# tube-driver.net
KiCad netlist of a schematic drawn in Altium Designer
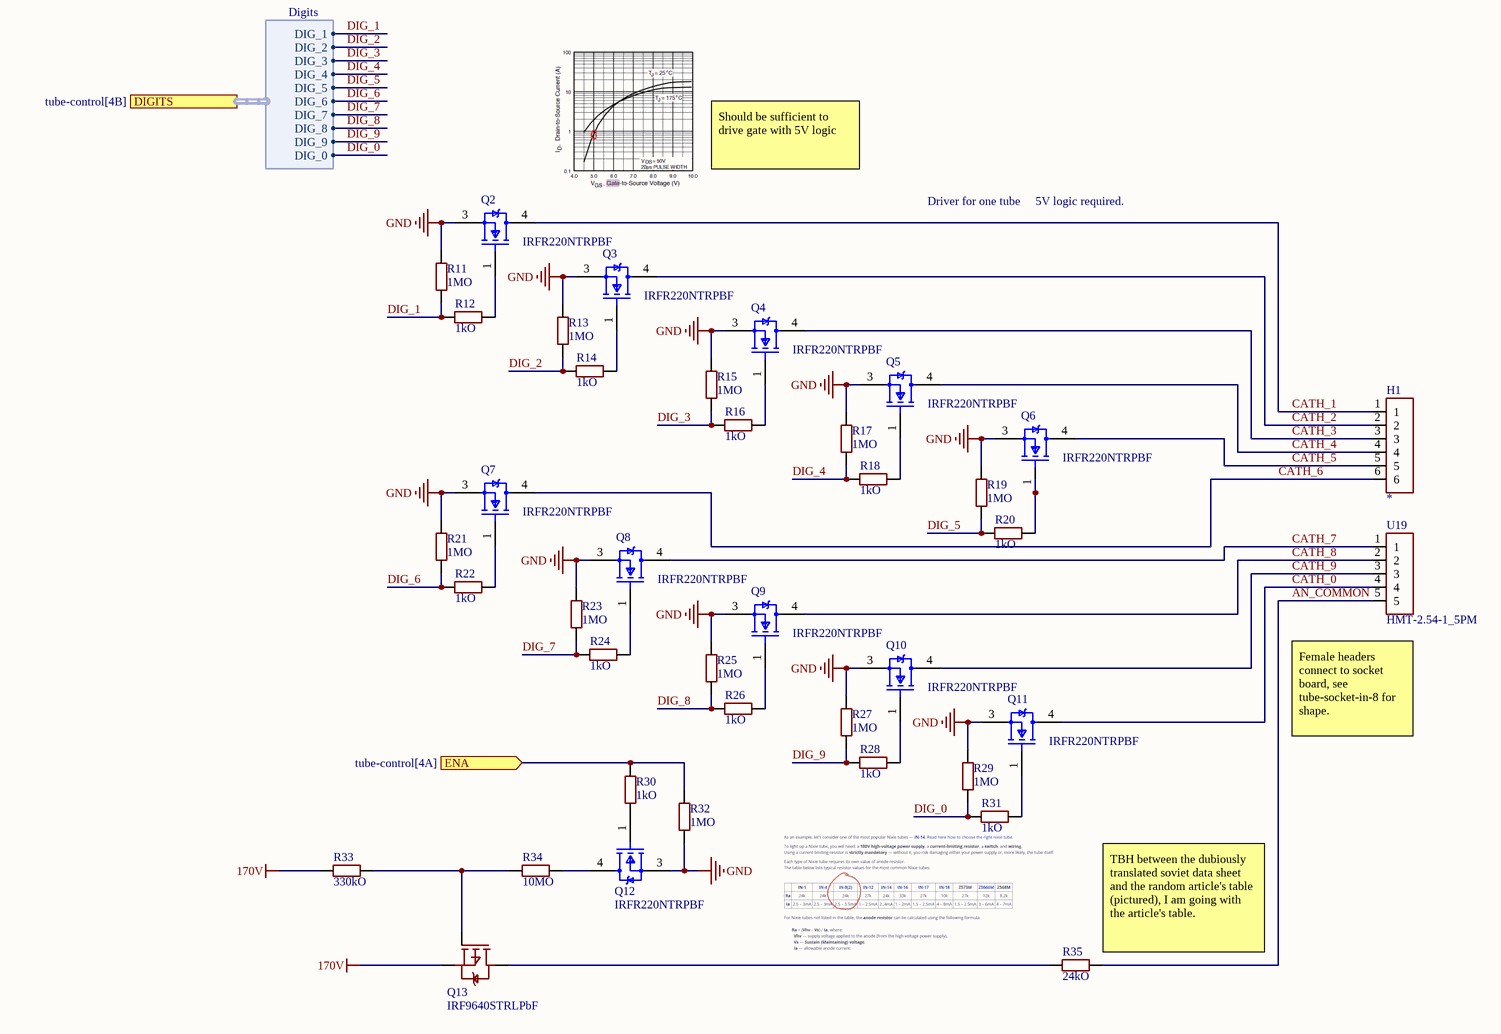
[diagram p0: tube-driver.SchDoc]

(export (version "E")
  (design (tool "Eeschema 10.0.6"))
  (components
    (comp (ref "H1")
      (value "2.54-1_6P")
      (footprint "2.54-1_6P")
      (fields
        (field (name "ALTIUM_VALUE") "*")
        (field (name "JLCPCB PART #") "C40877")
        (field (name "MANUFACTURER PART NUMBER") "2.54-1*6P")
        (field (name "MANUFACTURER") "BOOMELE(Boom Precision Elec)")
      )
      (libsource (lib "2.54-1_6P") (part "2.54-1_6P"))
    )
    (comp (ref "Q2")
      (value "IRFR220NTRPBF")
      (footprint "FP-PG-TO252-3-MFG")
      (description "MOSFET N-CH 200V 5A DPAK")
      (fields
        (field (name "MANUFACTURER") "Infineon")
        (field (name "OCTOPART") "https://octopart.com/irfr220ntrpbf-infineon-65874086")
      )
      (libsource (lib "Altium Content Vault") (part "2f21c11e83d30f418bb422e5a3b3d11"))
    )
    (comp (ref "Q3")
      (value "IRFR220NTRPBF")
      (footprint "FP-PG-TO252-3-MFG")
      (description "MOSFET N-CH 200V 5A DPAK")
      (fields
        (field (name "MANUFACTURER") "Infineon")
        (field (name "OCTOPART") "https://octopart.com/irfr220ntrpbf-infineon-65874086")
      )
      (libsource (lib "Altium Content Vault") (part "2f21c11e83d30f418bb422e5a3b3d11"))
    )
    (comp (ref "Q4")
      (value "IRFR220NTRPBF")
      (footprint "FP-PG-TO252-3-MFG")
      (description "MOSFET N-CH 200V 5A DPAK")
      (fields
        (field (name "MANUFACTURER") "Infineon")
        (field (name "OCTOPART") "https://octopart.com/irfr220ntrpbf-infineon-65874086")
      )
      (libsource (lib "Altium Content Vault") (part "2f21c11e83d30f418bb422e5a3b3d11"))
    )
    (comp (ref "Q5")
      (value "IRFR220NTRPBF")
      (footprint "FP-PG-TO252-3-MFG")
      (description "MOSFET N-CH 200V 5A DPAK")
      (fields
        (field (name "MANUFACTURER") "Infineon")
        (field (name "OCTOPART") "https://octopart.com/irfr220ntrpbf-infineon-65874086")
      )
      (libsource (lib "Altium Content Vault") (part "2f21c11e83d30f418bb422e5a3b3d11"))
    )
    (comp (ref "Q6")
      (value "IRFR220NTRPBF")
      (footprint "FP-PG-TO252-3-MFG")
      (description "MOSFET N-CH 200V 5A DPAK")
      (fields
        (field (name "MANUFACTURER") "Infineon")
        (field (name "OCTOPART") "https://octopart.com/irfr220ntrpbf-infineon-65874086")
      )
      (libsource (lib "Altium Content Vault") (part "2f21c11e83d30f418bb422e5a3b3d11"))
    )
    (comp (ref "Q7")
      (value "IRFR220NTRPBF")
      (footprint "FP-PG-TO252-3-MFG")
      (description "MOSFET N-CH 200V 5A DPAK")
      (fields
        (field (name "MANUFACTURER") "Infineon")
        (field (name "OCTOPART") "https://octopart.com/irfr220ntrpbf-infineon-65874086")
      )
      (libsource (lib "Altium Content Vault") (part "2f21c11e83d30f418bb422e5a3b3d11"))
    )
    (comp (ref "Q8")
      (value "IRFR220NTRPBF")
      (footprint "FP-PG-TO252-3-MFG")
      (description "MOSFET N-CH 200V 5A DPAK")
      (fields
        (field (name "MANUFACTURER") "Infineon")
        (field (name "OCTOPART") "https://octopart.com/irfr220ntrpbf-infineon-65874086")
      )
      (libsource (lib "Altium Content Vault") (part "2f21c11e83d30f418bb422e5a3b3d11"))
    )
    (comp (ref "Q9")
      (value "IRFR220NTRPBF")
      (footprint "FP-PG-TO252-3-MFG")
      (description "MOSFET N-CH 200V 5A DPAK")
      (fields
        (field (name "MANUFACTURER") "Infineon")
        (field (name "OCTOPART") "https://octopart.com/irfr220ntrpbf-infineon-65874086")
      )
      (libsource (lib "Altium Content Vault") (part "2f21c11e83d30f418bb422e5a3b3d11"))
    )
    (comp (ref "Q10")
      (value "IRFR220NTRPBF")
      (footprint "FP-PG-TO252-3-MFG")
      (description "MOSFET N-CH 200V 5A DPAK")
      (fields
        (field (name "MANUFACTURER") "Infineon")
        (field (name "OCTOPART") "https://octopart.com/irfr220ntrpbf-infineon-65874086")
      )
      (libsource (lib "Altium Content Vault") (part "2f21c11e83d30f418bb422e5a3b3d11"))
    )
    (comp (ref "Q11")
      (value "IRFR220NTRPBF")
      (footprint "FP-PG-TO252-3-MFG")
      (description "MOSFET N-CH 200V 5A DPAK")
      (fields
        (field (name "MANUFACTURER") "Infineon")
        (field (name "OCTOPART") "https://octopart.com/irfr220ntrpbf-infineon-65874086")
      )
      (libsource (lib "Altium Content Vault") (part "2f21c11e83d30f418bb422e5a3b3d11"))
    )
    (comp (ref "Q12")
      (value "IRFR220NTRPBF")
      (footprint "FP-PG-TO252-3-MFG")
      (description "MOSFET N-CH 200V 5A DPAK")
      (fields
        (field (name "MANUFACTURER") "Infineon")
        (field (name "OCTOPART") "https://octopart.com/irfr220ntrpbf-infineon-65874086")
      )
      (libsource (lib "Altium Content Vault") (part "2f21c11e83d30f418bb422e5a3b3d11"))
    )
    (comp (ref "Q13")
      (value "IRF9640STRLPbF")
      (footprint "IRF9640STRLPbF")
      (fields (field (name "JLCPCB PART #") "C2629") (field (name "MANUFACTURER") "Vishay Intertech"))
      (libsource (lib "IRF9640STRLPbF") (part "IRF9640STRLPbF"))
    )
    (comp (ref "R11")
      (value "1MO")
      (footprint "0402WGF1004TCE")
      (fields
        (field (name "JLCPCB PART #") "C26083")
        (field (name "MANUFACTURER PART NUMBER") "0402WGF1004TCE")
        (field (name "MANUFACTURER") "UNI-ROYAL(Uniroyal Elec)")
      )
      (libsource (lib "0402WGF1004TCE") (part "0402WGF1004TCE"))
    )
    (comp (ref "R12")
      (value "1kO")
      (footprint "0402WGF1001TCE")
      (fields
        (field (name "JLCPCB PART #") "C11702")
        (field (name "MANUFACTURER PART NUMBER") "0402WGF1001TCE")
        (field (name "MANUFACTURER") "UNI-ROYAL(Uniroyal Elec)")
      )
      (libsource (lib "0402WGF1001TCE") (part "0402WGF1001TCE"))
    )
    (comp (ref "R13")
      (value "1MO")
      (footprint "0402WGF1004TCE")
      (fields
        (field (name "JLCPCB PART #") "C26083")
        (field (name "MANUFACTURER PART NUMBER") "0402WGF1004TCE")
        (field (name "MANUFACTURER") "UNI-ROYAL(Uniroyal Elec)")
      )
      (libsource (lib "0402WGF1004TCE") (part "0402WGF1004TCE"))
    )
    (comp (ref "R14")
      (value "1kO")
      (footprint "0402WGF1001TCE")
      (fields
        (field (name "JLCPCB PART #") "C11702")
        (field (name "MANUFACTURER PART NUMBER") "0402WGF1001TCE")
        (field (name "MANUFACTURER") "UNI-ROYAL(Uniroyal Elec)")
      )
      (libsource (lib "0402WGF1001TCE") (part "0402WGF1001TCE"))
    )
    (comp (ref "R15")
      (value "1MO")
      (footprint "0402WGF1004TCE")
      (fields
        (field (name "JLCPCB PART #") "C26083")
        (field (name "MANUFACTURER PART NUMBER") "0402WGF1004TCE")
        (field (name "MANUFACTURER") "UNI-ROYAL(Uniroyal Elec)")
      )
      (libsource (lib "0402WGF1004TCE") (part "0402WGF1004TCE"))
    )
    (comp (ref "R16")
      (value "1kO")
      (footprint "0402WGF1001TCE")
      (fields
        (field (name "JLCPCB PART #") "C11702")
        (field (name "MANUFACTURER PART NUMBER") "0402WGF1001TCE")
        (field (name "MANUFACTURER") "UNI-ROYAL(Uniroyal Elec)")
      )
      (libsource (lib "0402WGF1001TCE") (part "0402WGF1001TCE"))
    )
    (comp (ref "R17")
      (value "1MO")
      (footprint "0402WGF1004TCE")
      (fields
        (field (name "JLCPCB PART #") "C26083")
        (field (name "MANUFACTURER PART NUMBER") "0402WGF1004TCE")
        (field (name "MANUFACTURER") "UNI-ROYAL(Uniroyal Elec)")
      )
      (libsource (lib "0402WGF1004TCE") (part "0402WGF1004TCE"))
    )
    (comp (ref "R18")
      (value "1kO")
      (footprint "0402WGF1001TCE")
      (fields
        (field (name "JLCPCB PART #") "C11702")
        (field (name "MANUFACTURER PART NUMBER") "0402WGF1001TCE")
        (field (name "MANUFACTURER") "UNI-ROYAL(Uniroyal Elec)")
      )
      (libsource (lib "0402WGF1001TCE") (part "0402WGF1001TCE"))
    )
    (comp (ref "R19")
      (value "1MO")
      (footprint "0402WGF1004TCE")
      (fields
        (field (name "JLCPCB PART #") "C26083")
        (field (name "MANUFACTURER PART NUMBER") "0402WGF1004TCE")
        (field (name "MANUFACTURER") "UNI-ROYAL(Uniroyal Elec)")
      )
      (libsource (lib "0402WGF1004TCE") (part "0402WGF1004TCE"))
    )
    (comp (ref "R20")
      (value "1kO")
      (footprint "0402WGF1001TCE")
      (fields
        (field (name "JLCPCB PART #") "C11702")
        (field (name "MANUFACTURER PART NUMBER") "0402WGF1001TCE")
        (field (name "MANUFACTURER") "UNI-ROYAL(Uniroyal Elec)")
      )
      (libsource (lib "0402WGF1001TCE") (part "0402WGF1001TCE"))
    )
    (comp (ref "R21")
      (value "1MO")
      (footprint "0402WGF1004TCE")
      (fields
        (field (name "JLCPCB PART #") "C26083")
        (field (name "MANUFACTURER PART NUMBER") "0402WGF1004TCE")
        (field (name "MANUFACTURER") "UNI-ROYAL(Uniroyal Elec)")
      )
      (libsource (lib "0402WGF1004TCE") (part "0402WGF1004TCE"))
    )
    (comp (ref "R22")
      (value "1kO")
      (footprint "0402WGF1001TCE")
      (fields
        (field (name "JLCPCB PART #") "C11702")
        (field (name "MANUFACTURER PART NUMBER") "0402WGF1001TCE")
        (field (name "MANUFACTURER") "UNI-ROYAL(Uniroyal Elec)")
      )
      (libsource (lib "0402WGF1001TCE") (part "0402WGF1001TCE"))
    )
    (comp (ref "R23")
      (value "1MO")
      (footprint "0402WGF1004TCE")
      (fields
        (field (name "JLCPCB PART #") "C26083")
        (field (name "MANUFACTURER PART NUMBER") "0402WGF1004TCE")
        (field (name "MANUFACTURER") "UNI-ROYAL(Uniroyal Elec)")
      )
      (libsource (lib "0402WGF1004TCE") (part "0402WGF1004TCE"))
    )
    (comp (ref "R24")
      (value "1kO")
      (footprint "0402WGF1001TCE")
      (fields
        (field (name "JLCPCB PART #") "C11702")
        (field (name "MANUFACTURER PART NUMBER") "0402WGF1001TCE")
        (field (name "MANUFACTURER") "UNI-ROYAL(Uniroyal Elec)")
      )
      (libsource (lib "0402WGF1001TCE") (part "0402WGF1001TCE"))
    )
    (comp (ref "R25")
      (value "1MO")
      (footprint "0402WGF1004TCE")
      (fields
        (field (name "JLCPCB PART #") "C26083")
        (field (name "MANUFACTURER PART NUMBER") "0402WGF1004TCE")
        (field (name "MANUFACTURER") "UNI-ROYAL(Uniroyal Elec)")
      )
      (libsource (lib "0402WGF1004TCE") (part "0402WGF1004TCE"))
    )
    (comp (ref "R26")
      (value "1kO")
      (footprint "0402WGF1001TCE")
      (fields
        (field (name "JLCPCB PART #") "C11702")
        (field (name "MANUFACTURER PART NUMBER") "0402WGF1001TCE")
        (field (name "MANUFACTURER") "UNI-ROYAL(Uniroyal Elec)")
      )
      (libsource (lib "0402WGF1001TCE") (part "0402WGF1001TCE"))
    )
    (comp (ref "R27")
      (value "1MO")
      (footprint "0402WGF1004TCE")
      (fields
        (field (name "JLCPCB PART #") "C26083")
        (field (name "MANUFACTURER PART NUMBER") "0402WGF1004TCE")
        (field (name "MANUFACTURER") "UNI-ROYAL(Uniroyal Elec)")
      )
      (libsource (lib "0402WGF1004TCE") (part "0402WGF1004TCE"))
    )
    (comp (ref "R28")
      (value "1kO")
      (footprint "0402WGF1001TCE")
      (fields
        (field (name "JLCPCB PART #") "C11702")
        (field (name "MANUFACTURER PART NUMBER") "0402WGF1001TCE")
        (field (name "MANUFACTURER") "UNI-ROYAL(Uniroyal Elec)")
      )
      (libsource (lib "0402WGF1001TCE") (part "0402WGF1001TCE"))
    )
    (comp (ref "R29")
      (value "1MO")
      (footprint "0402WGF1004TCE")
      (fields
        (field (name "JLCPCB PART #") "C26083")
        (field (name "MANUFACTURER PART NUMBER") "0402WGF1004TCE")
        (field (name "MANUFACTURER") "UNI-ROYAL(Uniroyal Elec)")
      )
      (libsource (lib "0402WGF1004TCE") (part "0402WGF1004TCE"))
    )
    (comp (ref "R30")
      (value "1kO")
      (footprint "0402WGF1001TCE")
      (fields
        (field (name "JLCPCB PART #") "C11702")
        (field (name "MANUFACTURER PART NUMBER") "0402WGF1001TCE")
        (field (name "MANUFACTURER") "UNI-ROYAL(Uniroyal Elec)")
      )
      (libsource (lib "") (part "0402WGF1001TCE_1"))
    )
    (comp (ref "R31")
      (value "1kO")
      (footprint "0402WGF1001TCE")
      (fields
        (field (name "JLCPCB PART #") "C11702")
        (field (name "MANUFACTURER PART NUMBER") "0402WGF1001TCE")
        (field (name "MANUFACTURER") "UNI-ROYAL(Uniroyal Elec)")
      )
      (libsource (lib "0402WGF1001TCE") (part "0402WGF1001TCE"))
    )
    (comp (ref "R32")
      (value "1MO")
      (footprint "0402WGF1004TCE")
      (fields
        (field (name "JLCPCB PART #") "C26083")
        (field (name "MANUFACTURER PART NUMBER") "0402WGF1004TCE")
        (field (name "MANUFACTURER") "UNI-ROYAL(Uniroyal Elec)")
      )
      (libsource (lib "0402WGF1004TCE") (part "0402WGF1004TCE"))
    )
    (comp (ref "R33")
      (value "330kO")
      (footprint "0603WAF3303T5E")
      (fields
        (field (name "JLCPCB PART #") "C23137")
        (field (name "MANUFACTURER PART NUMBER") "0603WAF3303T5E")
        (field (name "MANUFACTURER") "UNI-ROYAL(Uniroyal Elec)")
      )
      (libsource (lib "0603WAF3303T5E") (part "0603WAF3303T5E"))
    )
    (comp (ref "R34")
      (value "10MO")
      (footprint "0603WAF1005T5E")
      (fields
        (field (name "JLCPCB PART #") "C7250")
        (field (name "MANUFACTURER PART NUMBER") "0603WAF1005T5E")
        (field (name "MANUFACTURER") "UNI-ROYAL(Uniroyal Elec)")
      )
      (libsource (lib "0603WAF1005T5E") (part "0603WAF1005T5E"))
    )
    (comp (ref "R35")
      (value "24kO")
      (footprint "0603WAF2402T5E")
      (fields
        (field (name "JLCPCB PART #") "C23352")
        (field (name "MANUFACTURER PART NUMBER") "0603WAF2402T5E")
        (field (name "MANUFACTURER") "UNI-ROYAL(Uniroyal Elec)")
      )
      (libsource (lib "0603WAF2402T5E") (part "0603WAF2402T5E"))
    )
    (comp (ref "U19")
      (value "HMT-2.54-1_5PM")
      (footprint "HMT-2.54-1_5PM")
      (fields
        (field (name "JLCPCB PART #") "C54620386")
        (field (name "MANUFACTURER PART NUMBER") "HMT-2.54-1*5PM")
        (field (name "MANUFACTURER") "HMTCONN")
      )
      (libsource (lib "HMT-2.54-1_5PM") (part "HMT-2.54-1_5PM"))
    )
  )
  (nets
    (net (code "2") (name "/AN_COMMON") (class "Default")
      (node (ref "R35") (pin "2") (pinfunction "2_2") (pintype "passive"))
      (node (ref "U19") (pin "5") (pinfunction "5_5") (pintype "passive"))
    )
    (net (code "3") (name "/CATH_0") (class "Default")
      (node (ref "Q11") (pin "4") (pinfunction "DRAIN_4") (pintype "passive"))
      (node (ref "U19") (pin "4") (pinfunction "4_4") (pintype "passive"))
    )
    (net (code "4") (name "/CATH_1") (class "Default")
      (node (ref "H1") (pin "1") (pinfunction "1_1") (pintype "passive"))
      (node (ref "Q2") (pin "4") (pinfunction "DRAIN_4") (pintype "passive"))
    )
    (net (code "5") (name "/CATH_2") (class "Default")
      (node (ref "H1") (pin "2") (pinfunction "2_2") (pintype "passive"))
      (node (ref "Q3") (pin "4") (pinfunction "DRAIN_4") (pintype "passive"))
    )
    (net (code "6") (name "/CATH_3") (class "Default")
      (node (ref "H1") (pin "3") (pinfunction "3_3") (pintype "passive"))
      (node (ref "Q4") (pin "4") (pinfunction "DRAIN_4") (pintype "passive"))
    )
    (net (code "7") (name "/CATH_4") (class "Default")
      (node (ref "H1") (pin "4") (pinfunction "4_4") (pintype "passive"))
      (node (ref "Q5") (pin "4") (pinfunction "DRAIN_4") (pintype "passive"))
    )
    (net (code "8") (name "/CATH_5") (class "Default")
      (node (ref "H1") (pin "5") (pinfunction "5_5") (pintype "passive"))
      (node (ref "Q6") (pin "4") (pinfunction "DRAIN_4") (pintype "passive"))
    )
    (net (code "9") (name "/CATH_6") (class "Default")
      (node (ref "H1") (pin "6") (pinfunction "6_6") (pintype "passive"))
      (node (ref "Q7") (pin "4") (pinfunction "DRAIN_4") (pintype "passive"))
    )
    (net (code "10") (name "/CATH_7") (class "Default")
      (node (ref "Q8") (pin "4") (pinfunction "DRAIN_4") (pintype "passive"))
      (node (ref "U19") (pin "1") (pinfunction "1_1") (pintype "passive"))
    )
    (net (code "11") (name "/CATH_8") (class "Default")
      (node (ref "Q9") (pin "4") (pinfunction "DRAIN_4") (pintype "passive"))
      (node (ref "U19") (pin "2") (pinfunction "2_2") (pintype "passive"))
    )
    (net (code "12") (name "/CATH_9") (class "Default")
      (node (ref "Q10") (pin "4") (pinfunction "DRAIN_4") (pintype "passive"))
      (node (ref "U19") (pin "3") (pinfunction "3_3") (pintype "passive"))
    )
    (net (code "13") (name "/DIG_0") (class "Default")
      (node (ref "R29") (pin "1") (pinfunction "1_1") (pintype "passive"))
      (node (ref "R31") (pin "1") (pinfunction "1_1") (pintype "passive"))
    )
    (net (code "14") (name "/DIG_1") (class "Default")
      (node (ref "R11") (pin "1") (pinfunction "1_1") (pintype "passive"))
      (node (ref "R12") (pin "1") (pinfunction "1_1") (pintype "passive"))
    )
    (net (code "15") (name "/DIG_2") (class "Default")
      (node (ref "R13") (pin "1") (pinfunction "1_1") (pintype "passive"))
      (node (ref "R14") (pin "1") (pinfunction "1_1") (pintype "passive"))
    )
    (net (code "16") (name "/DIG_3") (class "Default")
      (node (ref "R15") (pin "1") (pinfunction "1_1") (pintype "passive"))
      (node (ref "R16") (pin "1") (pinfunction "1_1") (pintype "passive"))
    )
    (net (code "17") (name "/DIG_4") (class "Default")
      (node (ref "R17") (pin "1") (pinfunction "1_1") (pintype "passive"))
      (node (ref "R18") (pin "1") (pinfunction "1_1") (pintype "passive"))
    )
    (net (code "18") (name "/DIG_5") (class "Default")
      (node (ref "R19") (pin "1") (pinfunction "1_1") (pintype "passive"))
      (node (ref "R20") (pin "1") (pinfunction "1_1") (pintype "passive"))
    )
    (net (code "19") (name "/DIG_6") (class "Default")
      (node (ref "R21") (pin "1") (pinfunction "1_1") (pintype "passive"))
      (node (ref "R22") (pin "1") (pinfunction "1_1") (pintype "passive"))
    )
    (net (code "20") (name "/DIG_7") (class "Default")
      (node (ref "R23") (pin "1") (pinfunction "1_1") (pintype "passive"))
      (node (ref "R24") (pin "1") (pinfunction "1_1") (pintype "passive"))
    )
    (net (code "21") (name "/DIG_8") (class "Default")
      (node (ref "R25") (pin "1") (pinfunction "1_1") (pintype "passive"))
      (node (ref "R26") (pin "1") (pinfunction "1_1") (pintype "passive"))
    )
    (net (code "22") (name "/DIG_9") (class "Default")
      (node (ref "R27") (pin "1") (pinfunction "1_1") (pintype "passive"))
      (node (ref "R28") (pin "1") (pinfunction "1_1") (pintype "passive"))
    )
    (net (code "23") (name "/ENA") (class "Default")
      (node (ref "R30") (pin "2") (pinfunction "2_2") (pintype "passive"))
      (node (ref "R32") (pin "2") (pinfunction "2_2") (pintype "passive"))
    )
    (net (code "25") (name "170V") (class "Default")
      (node (ref "Q13") (pin "3") (pinfunction "S_3") (pintype "passive"))
      (node (ref "R33") (pin "1") (pinfunction "1_1") (pintype "passive"))
    )
    (net (code "26") (name "GND") (class "Default")
      (node (ref "Q10") (pin "3") (pinfunction "SOURCE_3") (pintype "passive"))
      (node (ref "Q11") (pin "3") (pinfunction "SOURCE_3") (pintype "passive"))
      (node (ref "Q12") (pin "3") (pinfunction "SOURCE_3") (pintype "passive"))
      (node (ref "Q2") (pin "3") (pinfunction "SOURCE_3") (pintype "passive"))
      (node (ref "Q3") (pin "3") (pinfunction "SOURCE_3") (pintype "passive"))
      (node (ref "Q4") (pin "3") (pinfunction "SOURCE_3") (pintype "passive"))
      (node (ref "Q5") (pin "3") (pinfunction "SOURCE_3") (pintype "passive"))
      (node (ref "Q6") (pin "3") (pinfunction "SOURCE_3") (pintype "passive"))
      (node (ref "Q7") (pin "3") (pinfunction "SOURCE_3") (pintype "passive"))
      (node (ref "Q8") (pin "3") (pinfunction "SOURCE_3") (pintype "passive"))
      (node (ref "Q9") (pin "3") (pinfunction "SOURCE_3") (pintype "passive"))
      (node (ref "R11") (pin "2") (pinfunction "2_2") (pintype "passive"))
      (node (ref "R13") (pin "2") (pinfunction "2_2") (pintype "passive"))
      (node (ref "R15") (pin "2") (pinfunction "2_2") (pintype "passive"))
      (node (ref "R17") (pin "2") (pinfunction "2_2") (pintype "passive"))
      (node (ref "R19") (pin "2") (pinfunction "2_2") (pintype "passive"))
      (node (ref "R21") (pin "2") (pinfunction "2_2") (pintype "passive"))
      (node (ref "R23") (pin "2") (pinfunction "2_2") (pintype "passive"))
      (node (ref "R25") (pin "2") (pinfunction "2_2") (pintype "passive"))
      (node (ref "R27") (pin "2") (pinfunction "2_2") (pintype "passive"))
      (node (ref "R29") (pin "2") (pinfunction "2_2") (pintype "passive"))
      (node (ref "R32") (pin "1") (pinfunction "1_1") (pintype "passive"))
    )
    (net (code "27") (name "Net-(Q2-GATE)") (class "Default")
      (node (ref "Q2") (pin "1") (pinfunction "GATE_1") (pintype "passive"))
      (node (ref "R12") (pin "2") (pinfunction "2_2") (pintype "passive"))
    )
    (net (code "28") (name "Net-(Q3-GATE)") (class "Default")
      (node (ref "Q3") (pin "1") (pinfunction "GATE_1") (pintype "passive"))
      (node (ref "R14") (pin "2") (pinfunction "2_2") (pintype "passive"))
    )
    (net (code "29") (name "Net-(Q4-GATE)") (class "Default")
      (node (ref "Q4") (pin "1") (pinfunction "GATE_1") (pintype "passive"))
      (node (ref "R16") (pin "2") (pinfunction "2_2") (pintype "passive"))
    )
    (net (code "30") (name "Net-(Q5-GATE)") (class "Default")
      (node (ref "Q5") (pin "1") (pinfunction "GATE_1") (pintype "passive"))
      (node (ref "R18") (pin "2") (pinfunction "2_2") (pintype "passive"))
    )
    (net (code "31") (name "Net-(Q6-GATE)") (class "Default")
      (node (ref "Q6") (pin "1") (pinfunction "GATE_1") (pintype "passive"))
      (node (ref "R20") (pin "2") (pinfunction "2_2") (pintype "passive"))
    )
    (net (code "32") (name "Net-(Q7-GATE)") (class "Default")
      (node (ref "Q7") (pin "1") (pinfunction "GATE_1") (pintype "passive"))
      (node (ref "R22") (pin "2") (pinfunction "2_2") (pintype "passive"))
    )
    (net (code "33") (name "Net-(Q8-GATE)") (class "Default")
      (node (ref "Q8") (pin "1") (pinfunction "GATE_1") (pintype "passive"))
      (node (ref "R24") (pin "2") (pinfunction "2_2") (pintype "passive"))
    )
    (net (code "34") (name "Net-(Q9-GATE)") (class "Default")
      (node (ref "Q9") (pin "1") (pinfunction "GATE_1") (pintype "passive"))
      (node (ref "R26") (pin "2") (pinfunction "2_2") (pintype "passive"))
    )
    (net (code "35") (name "Net-(Q10-GATE)") (class "Default")
      (node (ref "Q10") (pin "1") (pinfunction "GATE_1") (pintype "passive"))
      (node (ref "R28") (pin "2") (pinfunction "2_2") (pintype "passive"))
    )
    (net (code "36") (name "Net-(Q11-GATE)") (class "Default")
      (node (ref "Q11") (pin "1") (pinfunction "GATE_1") (pintype "passive"))
      (node (ref "R31") (pin "2") (pinfunction "2_2") (pintype "passive"))
    )
    (net (code "37") (name "Net-(Q12-DRAIN)") (class "Default")
      (node (ref "Q12") (pin "4") (pinfunction "DRAIN_4") (pintype "passive"))
      (node (ref "R34") (pin "2") (pinfunction "2_2") (pintype "passive"))
    )
    (net (code "38") (name "Net-(Q12-GATE)") (class "Default")
      (node (ref "Q12") (pin "1") (pinfunction "GATE_1") (pintype "passive"))
      (node (ref "R30") (pin "1") (pinfunction "1_1") (pintype "passive"))
    )
    (net (code "39") (name "Net-(Q13-D)") (class "Default")
      (node (ref "Q13") (pin "4") (pinfunction "D_4") (pintype "passive"))
      (node (ref "R35") (pin "1") (pinfunction "1_1") (pintype "passive"))
    )
    (net (code "40") (name "Net-(Q13-G)") (class "Default")
      (node (ref "Q13") (pin "1") (pinfunction "G_1") (pintype "passive"))
      (node (ref "R33") (pin "2") (pinfunction "2_2") (pintype "passive"))
      (node (ref "R34") (pin "1") (pinfunction "1_1") (pintype "passive"))
    )
  )
)
